# v3_Shield.net
KiCad netlist of a schematic drawn in EAGLE
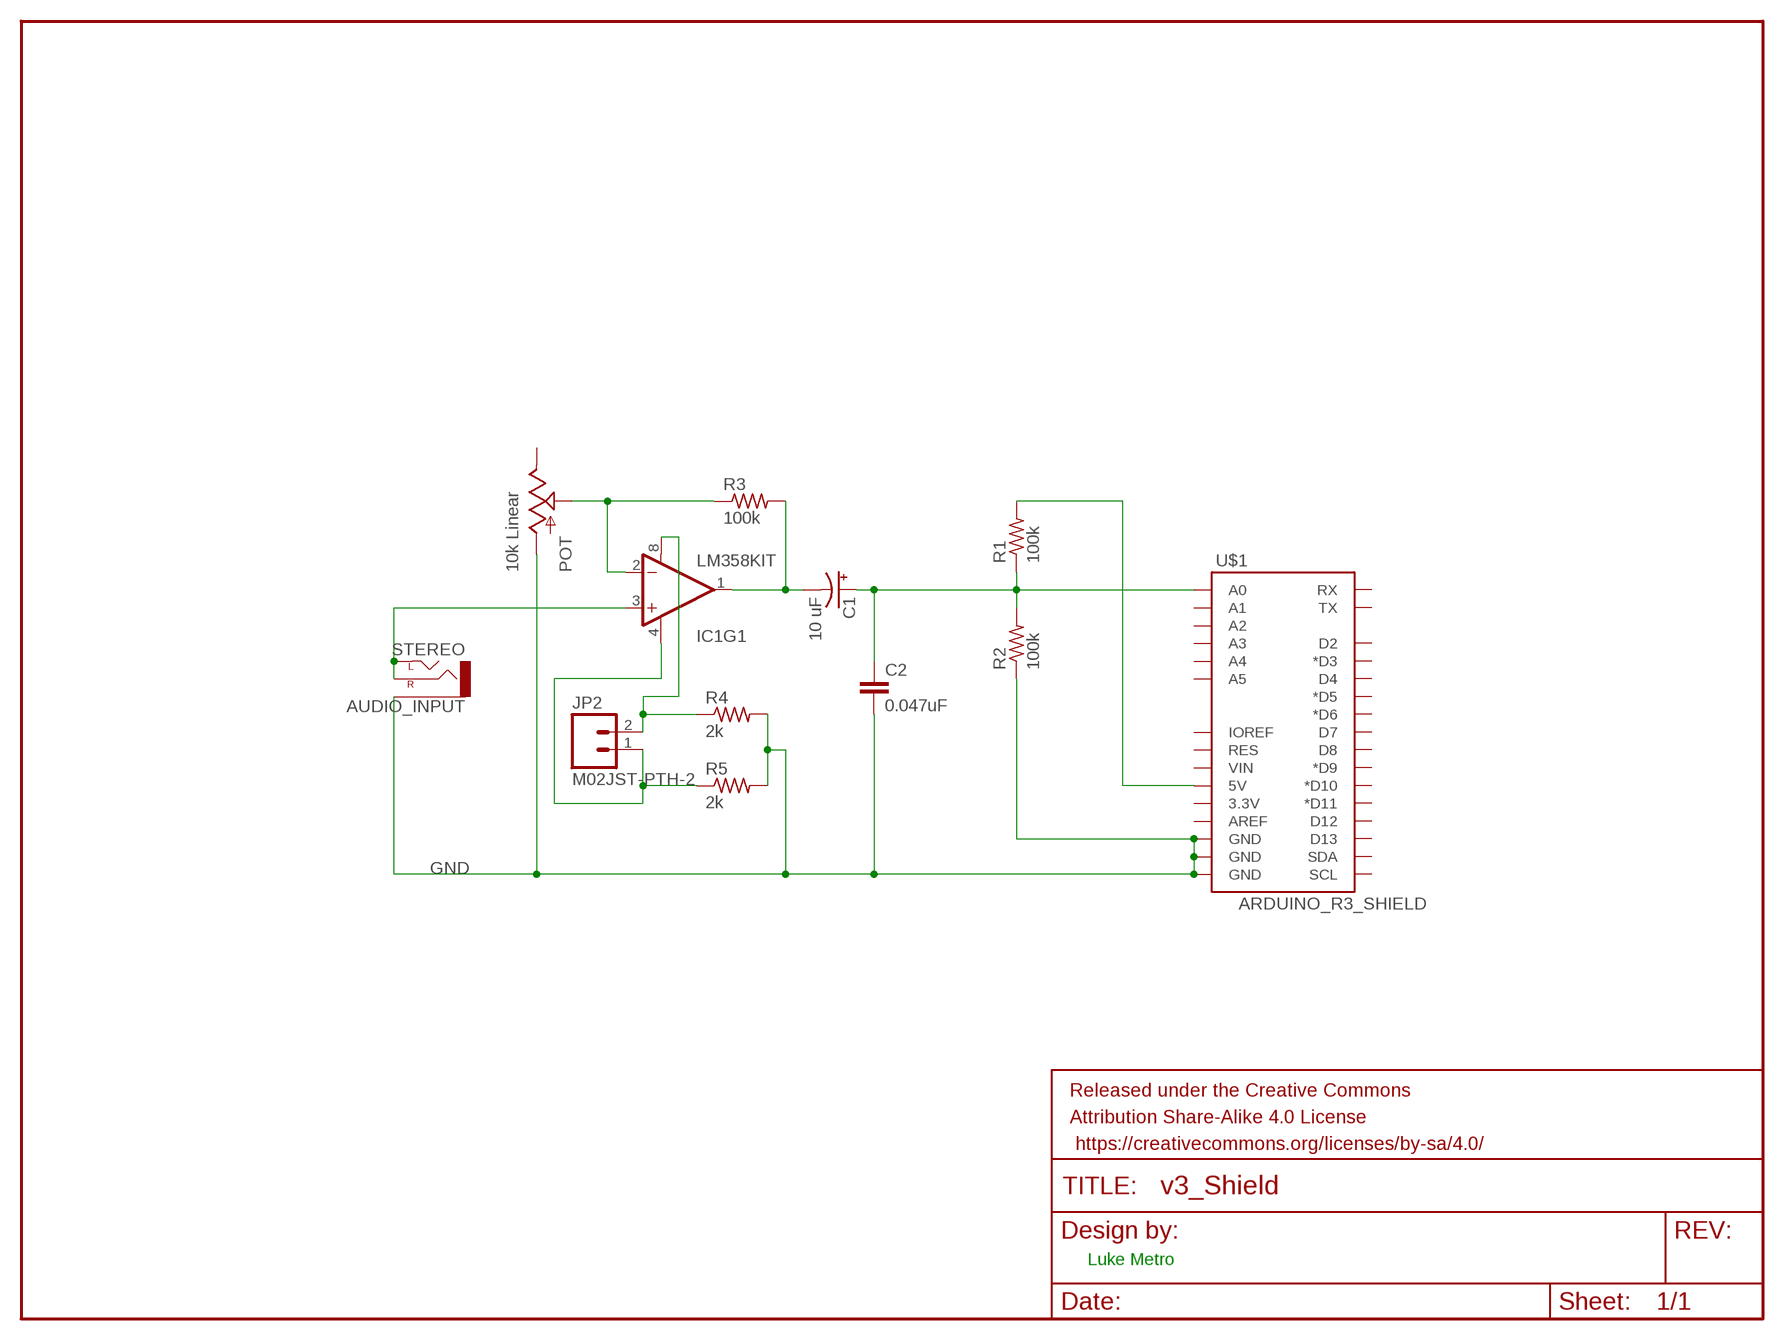
[diagram p0: schematic, sheet 1]

(export (version "E")
  (design (tool "Eeschema 10.0.6"))
  (components
    (comp (ref "AUDIO_INPUT")
      (value "STEREO")
      (footprint "eagle-import:AUDIO-JACK")
      (libsource (lib "eagle-import") (part "AUDIO-JACKPTH"))
    )
    (comp (ref "C1")
      (value "10 uF")
      (footprint "eagle-import:EIA6032")
      (libsource (lib "eagle-import") (part "CAP_POL6032"))
    )
    (comp (ref "C2")
      (value "0.047uF")
      (footprint "eagle-import:0402-CAP")
      (libsource (lib "eagle-import") (part "CAP0402-CAP"))
    )
    (comp (ref "FRAME1")
      (value "FRAME-LETTER")
      (footprint "eagle-import:CREATIVE_COMMONS")
      (libsource (lib "eagle-import") (part "FRAME-LETTER"))
    )
    (comp (ref "IC1")
      (value "LM358KIT")
      (footprint "eagle-import:DIP08-KIT")
      (libsource (lib "eagle-import") (part "LM358KIT"))
    )
    (comp (ref "JP2")
      (value "M02JST-PTH-2")
      (footprint "eagle-import:JST-2-PTH")
      (libsource (lib "eagle-import") (part "M02JST-PTH-2"))
    )
    (comp (ref "POT")
      (value "10k Linear")
      (footprint "eagle-import:ALPS_POT")
      (libsource (lib "eagle-import") (part "POT"))
    )
    (comp (ref "R1")
      (value "100k")
      (footprint "eagle-import:0805-THM")
      (libsource (lib "eagle-import") (part "FLIPFLOP-RES"))
    )
    (comp (ref "R2")
      (value "100k")
      (footprint "eagle-import:0805-THM")
      (libsource (lib "eagle-import") (part "FLIPFLOP-RES"))
    )
    (comp (ref "R3")
      (value "100k")
      (footprint "eagle-import:0805-THM")
      (libsource (lib "eagle-import") (part "FLIPFLOP-RES"))
    )
    (comp (ref "R4")
      (value "2k")
      (footprint "eagle-import:0805-THM")
      (libsource (lib "eagle-import") (part "FLIPFLOP-RES"))
    )
    (comp (ref "R5")
      (value "2k")
      (footprint "eagle-import:0805-THM")
      (libsource (lib "eagle-import") (part "FLIPFLOP-RES"))
    )
    (comp (ref "U$1")
      (value "ARDUINO_R3_SHIELD")
      (footprint "eagle-import:UNO_R3_SHIELD")
      (libsource (lib "eagle-import") (part "ARDUINO_R3_SHIELD"))
    )
  )
  (nets
    (net (code "1") (name "/GND") (class "Default")
      (node (ref "AUDIO_INPUT") (pin "SLEEVE") (pinfunction "SLEEVE_SLEEVE") (pintype "bidirectional"))
      (node (ref "C2") (pin "2") (pinfunction "2_2") (pintype "passive"))
      (node (ref "POT") (pin "P$3") (pinfunction "A_P$3") (pintype "passive"))
      (node (ref "R2") (pin "1") (pinfunction "1_1") (pintype "passive"))
      (node (ref "R4") (pin "2") (pinfunction "2_2") (pintype "passive"))
      (node (ref "R5") (pin "2") (pinfunction "2_2") (pintype "passive"))
      (node (ref "U$1") (pin "GND@0") (pinfunction "GND_GND@0") (pintype "bidirectional"))
      (node (ref "U$1") (pin "GND@1") (pinfunction "GND_GND@1") (pintype "bidirectional"))
      (node (ref "U$1") (pin "GND@2") (pinfunction "GND_GND@2") (pintype "bidirectional"))
    )
    (net (code "2") (name "Net-(AUDIO_INPUT-LEFT)") (class "Default")
      (node (ref "AUDIO_INPUT") (pin "RING") (pinfunction "RIGHT_RING") (pintype "bidirectional"))
      (node (ref "AUDIO_INPUT") (pin "TIP") (pinfunction "LEFT_TIP") (pintype "bidirectional"))
      (node (ref "IC1") (pin "3") (pinfunction "+IN_3") (pintype "input"))
    )
    (net (code "3") (name "Net-(C1-+)") (class "Default")
      (node (ref "C1") (pin "P$1") (pinfunction "+_P$1") (pintype "passive"))
      (node (ref "C2") (pin "1") (pinfunction "1_1") (pintype "passive"))
      (node (ref "R1") (pin "1") (pinfunction "1_1") (pintype "passive"))
      (node (ref "R2") (pin "2") (pinfunction "2_2") (pintype "passive"))
      (node (ref "U$1") (pin "A0") (pinfunction "A0_A0") (pintype "bidirectional"))
    )
    (net (code "4") (name "Net-(C1--)") (class "Default")
      (node (ref "C1") (pin "P$2") (pinfunction "-_P$2") (pintype "passive"))
      (node (ref "IC1") (pin "1") (pinfunction "OUT_1") (pintype "output"))
      (node (ref "R3") (pin "2") (pinfunction "2_2") (pintype "passive"))
    )
    (net (code "5") (name "Net-(IC1A--IN)") (class "Default")
      (node (ref "IC1") (pin "2") (pinfunction "-IN_2") (pintype "input"))
      (node (ref "POT") (pin "P$2") (pinfunction "S_P$2") (pintype "passive"))
      (node (ref "R3") (pin "1") (pinfunction "1_1") (pintype "passive"))
    )
    (net (code "6") (name "Net-(IC1A-V+)") (class "Default")
      (node (ref "IC1") (pin "8") (pinfunction "V+_8") (pintype "power_in"))
      (node (ref "JP2") (pin "2") (pinfunction "2_2") (pintype "passive"))
      (node (ref "R4") (pin "1") (pinfunction "1_1") (pintype "passive"))
    )
    (net (code "7") (name "Net-(IC1A-V-)") (class "Default")
      (node (ref "IC1") (pin "4") (pinfunction "V-_4") (pintype "power_in"))
      (node (ref "JP2") (pin "1") (pinfunction "1_1") (pintype "passive"))
      (node (ref "R5") (pin "1") (pinfunction "1_1") (pintype "passive"))
    )
    (net (code "8") (name "Net-(R1-Pad2)") (class "Default")
      (node (ref "R1") (pin "2") (pinfunction "2_2") (pintype "passive"))
      (node (ref "U$1") (pin "5V") (pinfunction "5V_5V") (pintype "bidirectional"))
    )
    (net (code "9") (name "unconnected-(POT-E-PadP$1)") (class "Default")
      (node (ref "POT") (pin "P$1") (pinfunction "E_P$1") (pintype "passive"))
    )
    (net (code "10") (name "unconnected-(U$1-*D3-PadD3)") (class "Default")
      (node (ref "U$1") (pin "D3") (pinfunction "*D3_D3") (pintype "bidirectional"))
    )
    (net (code "11") (name "unconnected-(U$1-*D5-PadD5)") (class "Default")
      (node (ref "U$1") (pin "D5") (pinfunction "*D5_D5") (pintype "bidirectional"))
    )
    (net (code "12") (name "unconnected-(U$1-*D6-PadD6)") (class "Default")
      (node (ref "U$1") (pin "D6") (pinfunction "*D6_D6") (pintype "bidirectional"))
    )
    (net (code "13") (name "unconnected-(U$1-*D9-PadD9)") (class "Default")
      (node (ref "U$1") (pin "D9") (pinfunction "*D9_D9") (pintype "bidirectional"))
    )
    (net (code "14") (name "unconnected-(U$1-*D10-PadD10)") (class "Default")
      (node (ref "U$1") (pin "D10") (pinfunction "*D10_D10") (pintype "bidirectional"))
    )
    (net (code "15") (name "unconnected-(U$1-*D11-PadD11)") (class "Default")
      (node (ref "U$1") (pin "D11") (pinfunction "*D11_D11") (pintype "bidirectional"))
    )
    (net (code "16") (name "unconnected-(U$1-Pad3.3V)") (class "Default")
      (node (ref "U$1") (pin "3.3V") (pinfunction "3.3V_3.3V") (pintype "bidirectional"))
    )
    (net (code "17") (name "unconnected-(U$1-PadA1)") (class "Default")
      (node (ref "U$1") (pin "A1") (pinfunction "A1_A1") (pintype "bidirectional"))
    )
    (net (code "18") (name "unconnected-(U$1-PadA2)") (class "Default")
      (node (ref "U$1") (pin "A2") (pinfunction "A2_A2") (pintype "bidirectional"))
    )
    (net (code "19") (name "unconnected-(U$1-PadA3)") (class "Default")
      (node (ref "U$1") (pin "A3") (pinfunction "A3_A3") (pintype "bidirectional"))
    )
    (net (code "20") (name "unconnected-(U$1-PadA4)") (class "Default")
      (node (ref "U$1") (pin "A4") (pinfunction "A4_A4") (pintype "bidirectional"))
    )
    (net (code "21") (name "unconnected-(U$1-PadA5)") (class "Default")
      (node (ref "U$1") (pin "A5") (pinfunction "A5_A5") (pintype "bidirectional"))
    )
    (net (code "22") (name "unconnected-(U$1-PadAREF)") (class "Default")
      (node (ref "U$1") (pin "AREF") (pinfunction "AREF_AREF") (pintype "bidirectional"))
    )
    (net (code "23") (name "unconnected-(U$1-PadD2)") (class "Default")
      (node (ref "U$1") (pin "D2") (pinfunction "D2_D2") (pintype "bidirectional"))
    )
    (net (code "24") (name "unconnected-(U$1-PadD4)") (class "Default")
      (node (ref "U$1") (pin "D4") (pinfunction "D4_D4") (pintype "bidirectional"))
    )
    (net (code "25") (name "unconnected-(U$1-PadD7)") (class "Default")
      (node (ref "U$1") (pin "D7") (pinfunction "D7_D7") (pintype "bidirectional"))
    )
    (net (code "26") (name "unconnected-(U$1-PadD8)") (class "Default")
      (node (ref "U$1") (pin "D8") (pinfunction "D8_D8") (pintype "bidirectional"))
    )
    (net (code "27") (name "unconnected-(U$1-PadD12)") (class "Default")
      (node (ref "U$1") (pin "D12") (pinfunction "D12_D12") (pintype "bidirectional"))
    )
    (net (code "28") (name "unconnected-(U$1-PadD13)") (class "Default")
      (node (ref "U$1") (pin "D13") (pinfunction "D13_D13") (pintype "bidirectional"))
    )
    (net (code "29") (name "unconnected-(U$1-PadIOREF)") (class "Default")
      (node (ref "U$1") (pin "IOREF") (pinfunction "IOREF_IOREF") (pintype "bidirectional"))
    )
    (net (code "30") (name "unconnected-(U$1-PadRES)") (class "Default")
      (node (ref "U$1") (pin "RES") (pinfunction "RES_RES") (pintype "bidirectional"))
    )
    (net (code "31") (name "unconnected-(U$1-PadRX)") (class "Default")
      (node (ref "U$1") (pin "RX") (pinfunction "RX_RX") (pintype "bidirectional"))
    )
    (net (code "32") (name "unconnected-(U$1-PadSCL)") (class "Default")
      (node (ref "U$1") (pin "SCL") (pinfunction "SCL_SCL") (pintype "bidirectional"))
    )
    (net (code "33") (name "unconnected-(U$1-PadSDA)") (class "Default")
      (node (ref "U$1") (pin "SDA") (pinfunction "SDA_SDA") (pintype "bidirectional"))
    )
    (net (code "34") (name "unconnected-(U$1-PadTX)") (class "Default")
      (node (ref "U$1") (pin "TX") (pinfunction "TX_TX") (pintype "bidirectional"))
    )
    (net (code "35") (name "unconnected-(U$1-PadVIN)") (class "Default")
      (node (ref "U$1") (pin "VIN") (pinfunction "VIN_VIN") (pintype "bidirectional"))
    )
  )
)
